# flight_comp_v5.net
KiCad netlist of a schematic drawn in EAGLE
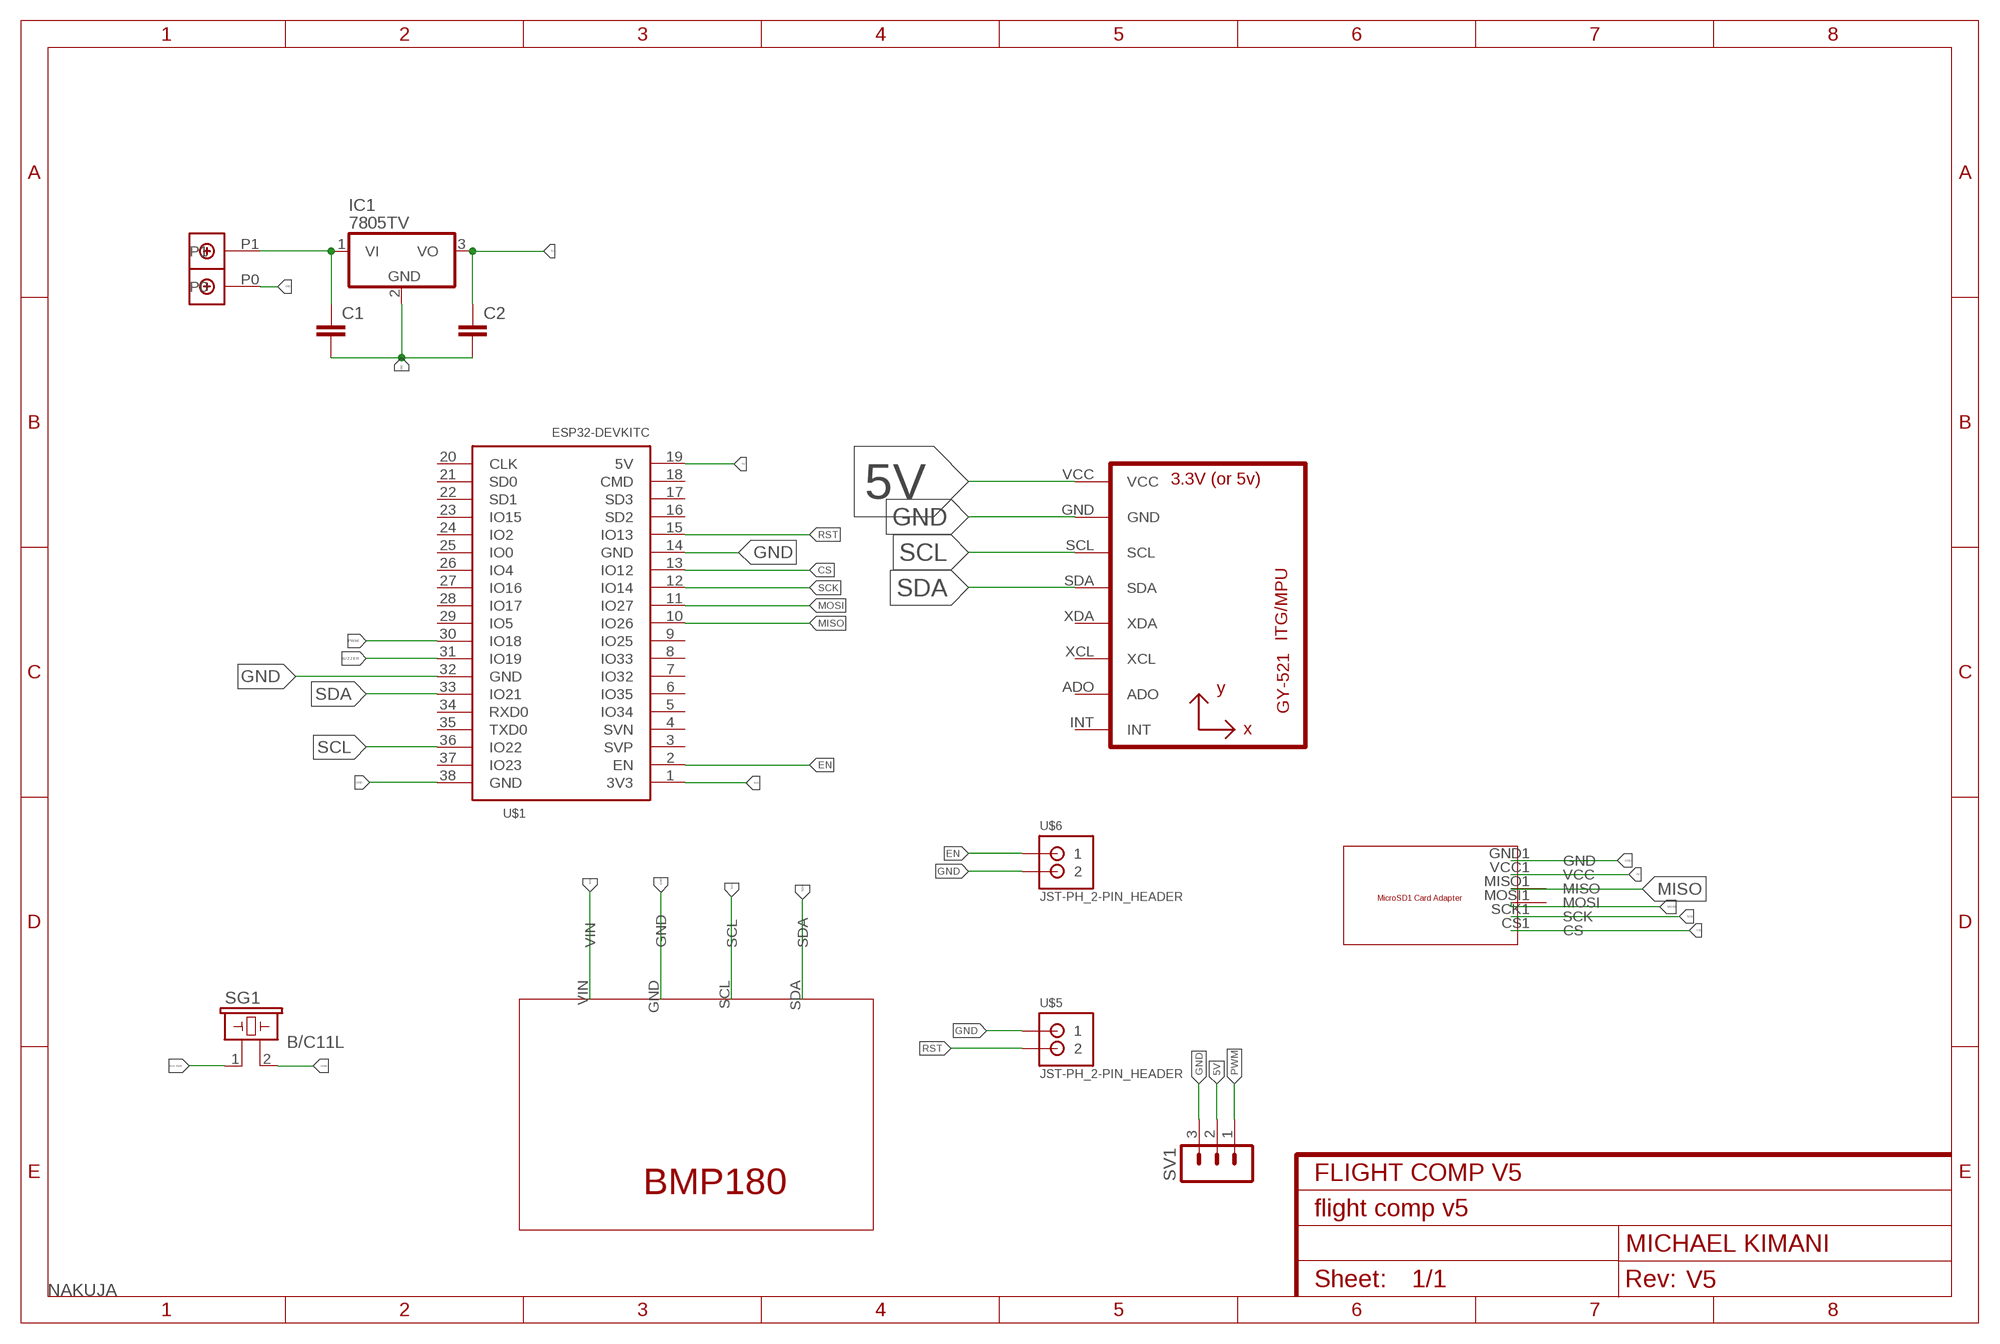
[diagram p0: schematic, sheet 1]

(export (version "E")
  (design (tool "Eeschema 10.0.6"))
  (components
    (comp (ref "C1")
      (value "C2,5-3")
      (footprint "eagle-import:C2.5-3")
      (libsource (lib "eagle-import") (part "C2,5-3"))
    )
    (comp (ref "C2")
      (value "C2,5-3")
      (footprint "eagle-import:C2.5-3")
      (libsource (lib "eagle-import") (part "C2,5-3"))
    )
    (comp (ref "IC1")
      (value "7805TV")
      (footprint "eagle-import:TO220V")
      (libsource (lib "eagle-import") (part "78TV05"))
    )
    (comp (ref "SG1")
      (value "B/C11L")
      (footprint "eagle-import:B_C11L")
      (libsource (lib "eagle-import") (part "B/C11L"))
    )
    (comp (ref "SV1")
      (value "MA03-1")
      (footprint "eagle-import:MA03-1")
      (libsource (lib "eagle-import") (part "MA03-1"))
    )
    (comp (ref "U$1")
      (value "ESP32DEVKITC")
      (footprint "eagle-import:ESP32-DEVKITC")
      (libsource (lib "eagle-import") (part "ESP32DEVKITC"))
    )
    (comp (ref "U$2")
      (value "MICROSDADAPTER")
      (footprint "eagle-import:MICROSDADAPTER")
      (libsource (lib "eagle-import") (part "MICROSDADAPTER"))
    )
    (comp (ref "U$3")
      (value "BMP180")
      (footprint "eagle-import:BMP180")
      (libsource (lib "eagle-import") (part "BMP180"))
    )
    (comp (ref "U$4")
      (value "DBCONN-1X2")
      (footprint "eagle-import:DBCONN-1X2")
      (libsource (lib "eagle-import") (part "DBCONN-1X2"))
    )
    (comp (ref "U$5")
      (value "JST-PH_2-PIN_HEADER")
      (footprint "eagle-import:JST_B2B-PH_HEADER")
      (libsource (lib "eagle-import") (part "JST-PH_2-PIN_HEADER"))
    )
    (comp (ref "U$6")
      (value "JST-PH_2-PIN_HEADER")
      (footprint "eagle-import:JST_B2B-PH_HEADER")
      (libsource (lib "eagle-import") (part "JST-PH_2-PIN_HEADER"))
    )
    (comp (ref "U1")
      (value "GY-521MPU6050")
      (footprint "eagle-import:GY-521")
      (libsource (lib "eagle-import") (part "GY-521MPU6050"))
    )
  )
  (nets
    (net (code "1") (name "3V3") (class "Default")
      (node (ref "U$1") (pin "1") (pinfunction "3V3_1") (pintype "bidirectional"))
      (node (ref "U$3") (pin "VIN") (pinfunction "VIN_VIN") (pintype "bidirectional"))
    )
    (net (code "2") (name "5V") (class "Default")
      (node (ref "C2") (pin "1") (pinfunction "1_1") (pintype "passive"))
      (node (ref "IC1") (pin "3") (pinfunction "VO_3") (pintype "passive"))
      (node (ref "SV1") (pin "2") (pinfunction "2_2") (pintype "passive"))
      (node (ref "U$1") (pin "19") (pinfunction "5V_19") (pintype "bidirectional"))
      (node (ref "U$2") (pin "VCC1") (pinfunction "VCC_VCC1") (pintype "bidirectional"))
      (node (ref "U1") (pin "VCC") (pinfunction "VCC_VCC") (pintype "bidirectional"))
    )
    (net (code "3") (name "BUZZER") (class "Default")
      (node (ref "SG1") (pin "1") (pinfunction "1_1") (pintype "passive"))
      (node (ref "U$1") (pin "31") (pinfunction "IO19_31") (pintype "bidirectional"))
    )
    (net (code "4") (name "CS") (class "Default")
      (node (ref "U$1") (pin "13") (pinfunction "IO12_13") (pintype "bidirectional"))
      (node (ref "U$2") (pin "CS1") (pinfunction "CS_CS1") (pintype "bidirectional"))
    )
    (net (code "5") (name "EN") (class "Default")
      (node (ref "U$1") (pin "2") (pinfunction "EN_2") (pintype "bidirectional"))
      (node (ref "U$6") (pin "P1") (pinfunction "1_P1") (pintype "bidirectional"))
    )
    (net (code "6") (name "GND") (class "Default")
      (node (ref "C1") (pin "2") (pinfunction "2_2") (pintype "passive"))
      (node (ref "C2") (pin "2") (pinfunction "2_2") (pintype "passive"))
      (node (ref "IC1") (pin "2") (pinfunction "GND_2") (pintype "passive"))
      (node (ref "SG1") (pin "2") (pinfunction "2_2") (pintype "passive"))
      (node (ref "SV1") (pin "3") (pinfunction "3_3") (pintype "passive"))
      (node (ref "U$1") (pin "14") (pinfunction "GND_14") (pintype "bidirectional"))
      (node (ref "U$1") (pin "32") (pinfunction "GND_32") (pintype "bidirectional"))
      (node (ref "U$1") (pin "38") (pinfunction "GND_38") (pintype "bidirectional"))
      (node (ref "U$2") (pin "GND1") (pinfunction "GND_GND1") (pintype "bidirectional"))
      (node (ref "U$3") (pin "GND") (pinfunction "GND_GND") (pintype "bidirectional"))
      (node (ref "U$4") (pin "P0") (pinfunction "P0_P0") (pintype "bidirectional"))
      (node (ref "U$5") (pin "P1") (pinfunction "1_P1") (pintype "bidirectional"))
      (node (ref "U$6") (pin "P2") (pinfunction "2_P2") (pintype "bidirectional"))
      (node (ref "U1") (pin "GND") (pinfunction "GND_GND") (pintype "bidirectional"))
    )
    (net (code "7") (name "MISO") (class "Default")
      (node (ref "U$1") (pin "10") (pinfunction "IO26_10") (pintype "bidirectional"))
      (node (ref "U$2") (pin "MISO1") (pinfunction "MISO_MISO1") (pintype "bidirectional"))
    )
    (net (code "8") (name "MOSI") (class "Default")
      (node (ref "U$1") (pin "11") (pinfunction "IO27_11") (pintype "bidirectional"))
      (node (ref "U$2") (pin "MOSI1") (pinfunction "MOSI_MOSI1") (pintype "bidirectional"))
    )
    (net (code "9") (name "Net-(IC1-VI)") (class "Default")
      (node (ref "C1") (pin "1") (pinfunction "1_1") (pintype "passive"))
      (node (ref "IC1") (pin "1") (pinfunction "VI_1") (pintype "input"))
      (node (ref "U$4") (pin "P1") (pinfunction "P1_P1") (pintype "bidirectional"))
    )
    (net (code "10") (name "PWM") (class "Default")
      (node (ref "SV1") (pin "1") (pinfunction "1_1") (pintype "passive"))
      (node (ref "U$1") (pin "30") (pinfunction "IO18_30") (pintype "bidirectional"))
    )
    (net (code "11") (name "RST") (class "Default")
      (node (ref "U$1") (pin "15") (pinfunction "IO13_15") (pintype "bidirectional"))
      (node (ref "U$5") (pin "P2") (pinfunction "2_P2") (pintype "bidirectional"))
    )
    (net (code "12") (name "SCK") (class "Default")
      (node (ref "U$1") (pin "12") (pinfunction "IO14_12") (pintype "bidirectional"))
      (node (ref "U$2") (pin "SCK1") (pinfunction "SCK_SCK1") (pintype "bidirectional"))
    )
    (net (code "13") (name "SCL") (class "Default")
      (node (ref "U$1") (pin "36") (pinfunction "IO22_36") (pintype "bidirectional"))
      (node (ref "U$3") (pin "SCL") (pinfunction "SCL_SCL") (pintype "bidirectional"))
      (node (ref "U1") (pin "SCL") (pinfunction "SCL_SCL") (pintype "bidirectional"))
    )
    (net (code "14") (name "SDA") (class "Default")
      (node (ref "U$1") (pin "33") (pinfunction "IO21_33") (pintype "bidirectional"))
      (node (ref "U$3") (pin "SDA") (pinfunction "SDA_SDA") (pintype "bidirectional"))
      (node (ref "U1") (pin "SDA") (pinfunction "SDA_SDA") (pintype "bidirectional"))
    )
    (net (code "15") (name "unconnected-(U$1-CLK-Pad20)") (class "Default")
      (node (ref "U$1") (pin "20") (pinfunction "CLK_20") (pintype "bidirectional"))
    )
    (net (code "16") (name "unconnected-(U$1-CMD-Pad18)") (class "Default")
      (node (ref "U$1") (pin "18") (pinfunction "CMD_18") (pintype "bidirectional"))
    )
    (net (code "17") (name "unconnected-(U$1-IO0-Pad25)") (class "Default")
      (node (ref "U$1") (pin "25") (pinfunction "IO0_25") (pintype "bidirectional"))
    )
    (net (code "18") (name "unconnected-(U$1-IO2-Pad24)") (class "Default")
      (node (ref "U$1") (pin "24") (pinfunction "IO2_24") (pintype "bidirectional"))
    )
    (net (code "19") (name "unconnected-(U$1-IO4-Pad26)") (class "Default")
      (node (ref "U$1") (pin "26") (pinfunction "IO4_26") (pintype "bidirectional"))
    )
    (net (code "20") (name "unconnected-(U$1-IO5-Pad29)") (class "Default")
      (node (ref "U$1") (pin "29") (pinfunction "IO5_29") (pintype "bidirectional"))
    )
    (net (code "21") (name "unconnected-(U$1-IO15-Pad23)") (class "Default")
      (node (ref "U$1") (pin "23") (pinfunction "IO15_23") (pintype "bidirectional"))
    )
    (net (code "22") (name "unconnected-(U$1-IO16-Pad27)") (class "Default")
      (node (ref "U$1") (pin "27") (pinfunction "IO16_27") (pintype "bidirectional"))
    )
    (net (code "23") (name "unconnected-(U$1-IO17-Pad28)") (class "Default")
      (node (ref "U$1") (pin "28") (pinfunction "IO17_28") (pintype "bidirectional"))
    )
    (net (code "24") (name "unconnected-(U$1-IO23-Pad37)") (class "Default")
      (node (ref "U$1") (pin "37") (pinfunction "IO23_37") (pintype "bidirectional"))
    )
    (net (code "25") (name "unconnected-(U$1-IO25-Pad9)") (class "Default")
      (node (ref "U$1") (pin "9") (pinfunction "IO25_9") (pintype "bidirectional"))
    )
    (net (code "26") (name "unconnected-(U$1-IO32-Pad7)") (class "Default")
      (node (ref "U$1") (pin "7") (pinfunction "IO32_7") (pintype "bidirectional"))
    )
    (net (code "27") (name "unconnected-(U$1-IO33-Pad8)") (class "Default")
      (node (ref "U$1") (pin "8") (pinfunction "IO33_8") (pintype "bidirectional"))
    )
    (net (code "28") (name "unconnected-(U$1-IO34-Pad5)") (class "Default")
      (node (ref "U$1") (pin "5") (pinfunction "IO34_5") (pintype "bidirectional"))
    )
    (net (code "29") (name "unconnected-(U$1-IO35-Pad6)") (class "Default")
      (node (ref "U$1") (pin "6") (pinfunction "IO35_6") (pintype "bidirectional"))
    )
    (net (code "30") (name "unconnected-(U$1-RXD0-Pad34)") (class "Default")
      (node (ref "U$1") (pin "34") (pinfunction "RXD0_34") (pintype "bidirectional"))
    )
    (net (code "31") (name "unconnected-(U$1-SD0-Pad21)") (class "Default")
      (node (ref "U$1") (pin "21") (pinfunction "SD0_21") (pintype "bidirectional"))
    )
    (net (code "32") (name "unconnected-(U$1-SD1-Pad22)") (class "Default")
      (node (ref "U$1") (pin "22") (pinfunction "SD1_22") (pintype "bidirectional"))
    )
    (net (code "33") (name "unconnected-(U$1-SD2-Pad16)") (class "Default")
      (node (ref "U$1") (pin "16") (pinfunction "SD2_16") (pintype "bidirectional"))
    )
    (net (code "34") (name "unconnected-(U$1-SD3-Pad17)") (class "Default")
      (node (ref "U$1") (pin "17") (pinfunction "SD3_17") (pintype "bidirectional"))
    )
    (net (code "35") (name "unconnected-(U$1-SVN-Pad4)") (class "Default")
      (node (ref "U$1") (pin "4") (pinfunction "SVN_4") (pintype "bidirectional"))
    )
    (net (code "36") (name "unconnected-(U$1-SVP-Pad3)") (class "Default")
      (node (ref "U$1") (pin "3") (pinfunction "SVP_3") (pintype "bidirectional"))
    )
    (net (code "37") (name "unconnected-(U$1-TXD0-Pad35)") (class "Default")
      (node (ref "U$1") (pin "35") (pinfunction "TXD0_35") (pintype "bidirectional"))
    )
    (net (code "38") (name "unconnected-(U1-PadADO)") (class "Default")
      (node (ref "U1") (pin "ADO") (pinfunction "ADO_ADO") (pintype "bidirectional"))
    )
    (net (code "39") (name "unconnected-(U1-PadINT)") (class "Default")
      (node (ref "U1") (pin "INT") (pinfunction "INT_INT") (pintype "bidirectional"))
    )
    (net (code "40") (name "unconnected-(U1-PadXCL)") (class "Default")
      (node (ref "U1") (pin "XCL") (pinfunction "XCL_XCL") (pintype "bidirectional"))
    )
    (net (code "41") (name "unconnected-(U1-PadXDA)") (class "Default")
      (node (ref "U1") (pin "XDA") (pinfunction "XDA_XDA") (pintype "bidirectional"))
    )
  )
)
